# Dragino-MS14-S-Relay-Board.net
KiCad netlist of a schematic drawn in EAGLE
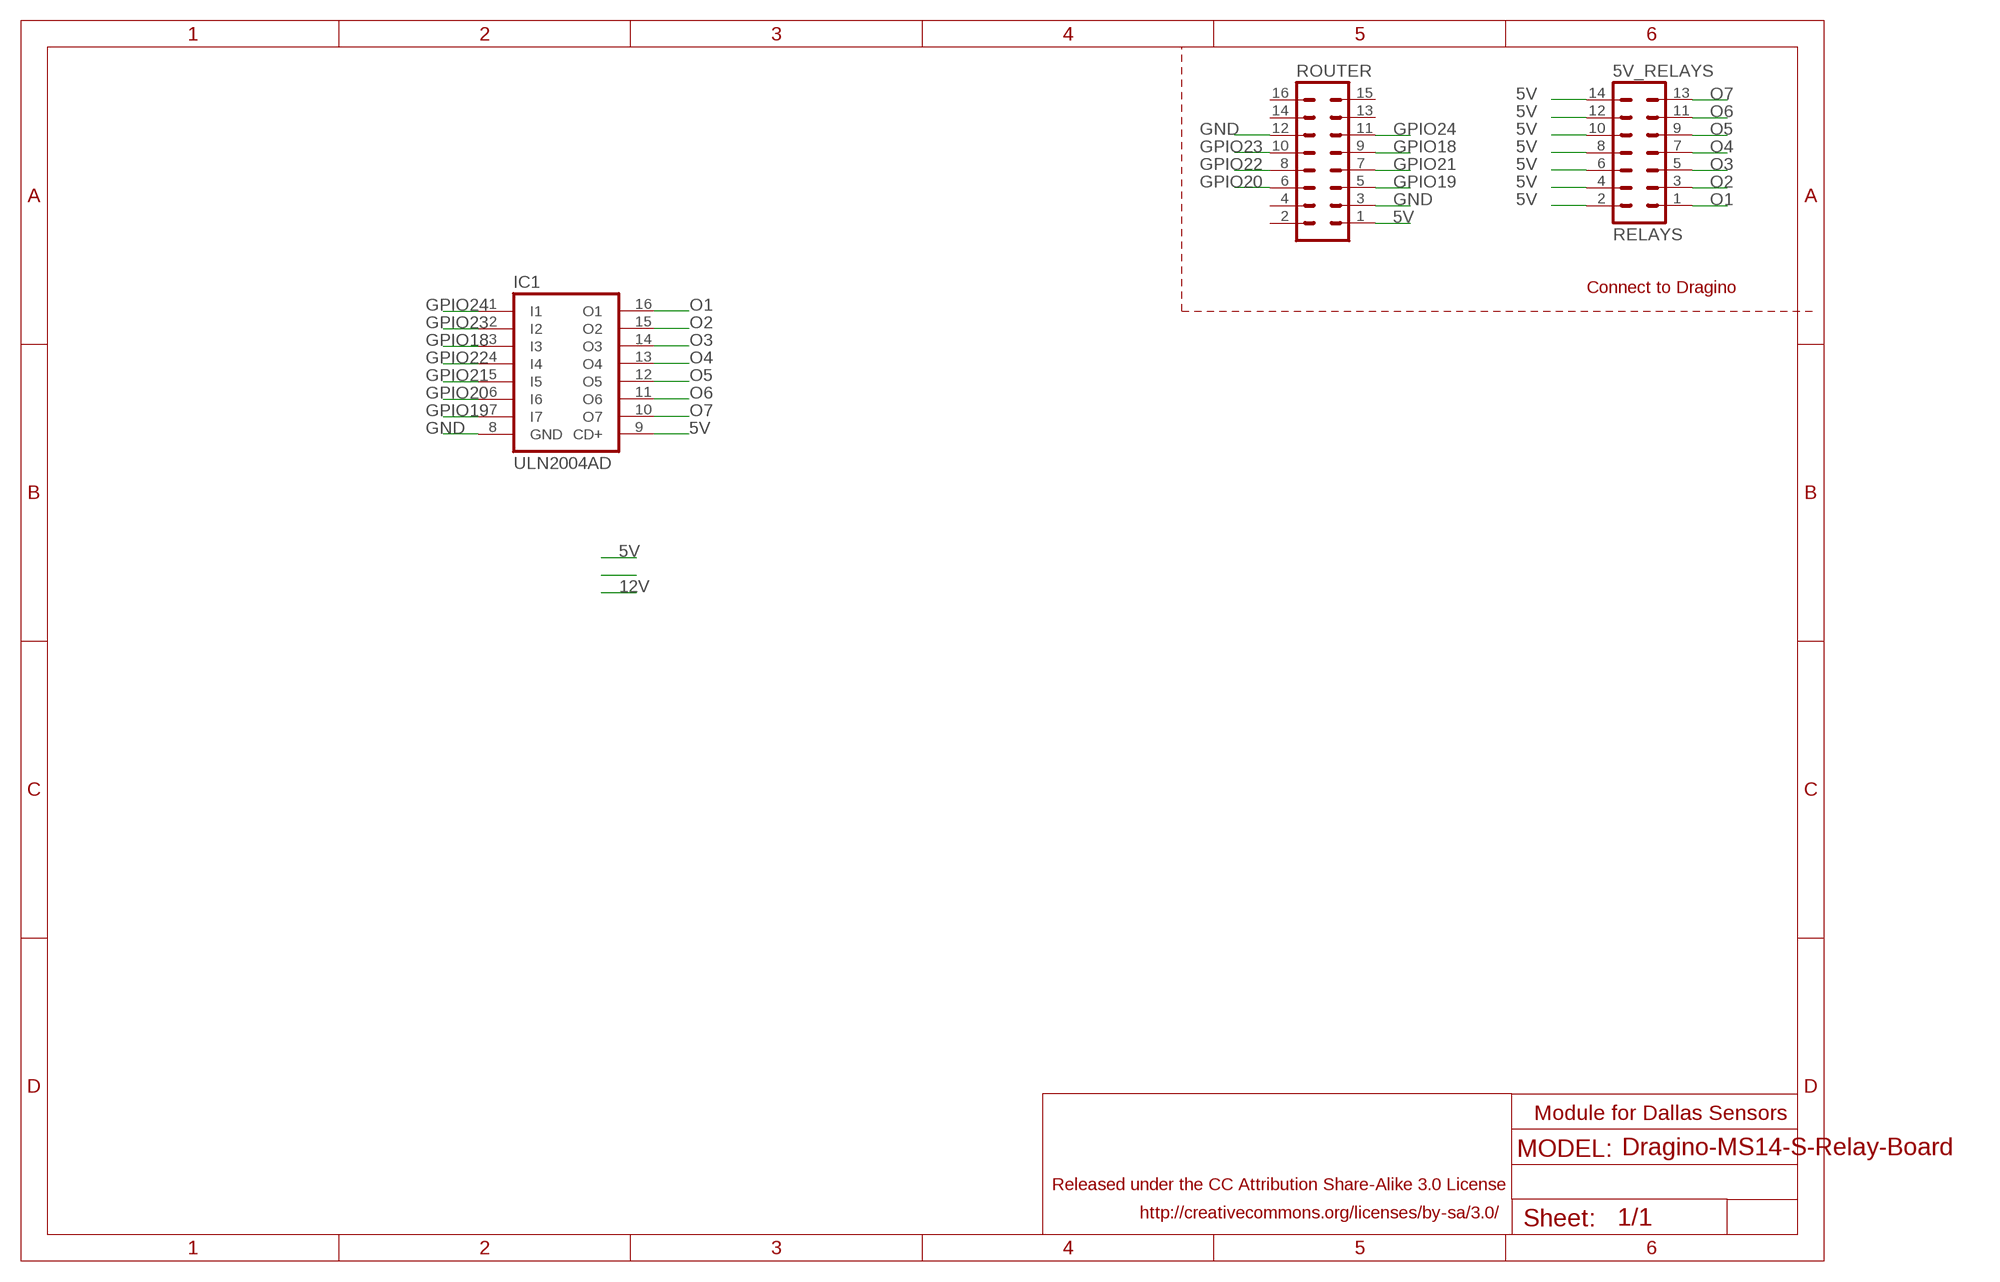
[diagram p0: schematic, sheet 1]

(export (version "E")
  (design (tool "Eeschema 10.0.6"))
  (components
    (comp (ref "5V_RELAYS")
      (value "RELAYS")
      (footprint "eagle-import:MA07-2")
      (libsource (lib "eagle-import") (part "MA07-2"))
    )
    (comp (ref "IC1")
      (value "ULN2004AD")
      (footprint "eagle-import:SO16")
      (libsource (lib "eagle-import") (part "ULN2004AD"))
    )
    (comp (ref "ROUTER")
      (value "MA08-2")
      (footprint "eagle-import:MA08-2")
      (libsource (lib "eagle-import") (part "MA08-2"))
    )
  )
  (nets
    (net (code "1") (name "/5V") (class "Default")
      (node (ref "5V_RELAYS") (pin "10") (pinfunction "10_10") (pintype "passive"))
      (node (ref "5V_RELAYS") (pin "12") (pinfunction "12_12") (pintype "passive"))
      (node (ref "5V_RELAYS") (pin "14") (pinfunction "14_14") (pintype "passive"))
      (node (ref "5V_RELAYS") (pin "2") (pinfunction "2_2") (pintype "passive"))
      (node (ref "5V_RELAYS") (pin "4") (pinfunction "4_4") (pintype "passive"))
      (node (ref "5V_RELAYS") (pin "6") (pinfunction "6_6") (pintype "passive"))
      (node (ref "5V_RELAYS") (pin "8") (pinfunction "8_8") (pintype "passive"))
      (node (ref "IC1") (pin "9") (pinfunction "CD+_9") (pintype "passive"))
      (node (ref "ROUTER") (pin "1") (pinfunction "1_1") (pintype "passive"))
    )
    (net (code "3") (name "/GND") (class "Default")
      (node (ref "IC1") (pin "8") (pinfunction "GND_8") (pintype "power_in"))
      (node (ref "ROUTER") (pin "12") (pinfunction "12_12") (pintype "passive"))
      (node (ref "ROUTER") (pin "3") (pinfunction "3_3") (pintype "passive"))
    )
    (net (code "4") (name "/GPIO18") (class "Default")
      (node (ref "IC1") (pin "3") (pinfunction "I3_3") (pintype "input"))
      (node (ref "ROUTER") (pin "9") (pinfunction "9_9") (pintype "passive"))
    )
    (net (code "5") (name "/GPIO19") (class "Default")
      (node (ref "IC1") (pin "7") (pinfunction "I7_7") (pintype "input"))
      (node (ref "ROUTER") (pin "5") (pinfunction "5_5") (pintype "passive"))
    )
    (net (code "6") (name "/GPIO20") (class "Default")
      (node (ref "IC1") (pin "6") (pinfunction "I6_6") (pintype "input"))
      (node (ref "ROUTER") (pin "6") (pinfunction "6_6") (pintype "passive"))
    )
    (net (code "7") (name "/GPIO21") (class "Default")
      (node (ref "IC1") (pin "5") (pinfunction "I5_5") (pintype "input"))
      (node (ref "ROUTER") (pin "7") (pinfunction "7_7") (pintype "passive"))
    )
    (net (code "8") (name "/GPIO22") (class "Default")
      (node (ref "IC1") (pin "4") (pinfunction "I4_4") (pintype "input"))
      (node (ref "ROUTER") (pin "8") (pinfunction "8_8") (pintype "passive"))
    )
    (net (code "9") (name "/GPIO23") (class "Default")
      (node (ref "IC1") (pin "2") (pinfunction "I2_2") (pintype "input"))
      (node (ref "ROUTER") (pin "10") (pinfunction "10_10") (pintype "passive"))
    )
    (net (code "10") (name "/GPIO24") (class "Default")
      (node (ref "IC1") (pin "1") (pinfunction "I1_1") (pintype "input"))
      (node (ref "ROUTER") (pin "11") (pinfunction "11_11") (pintype "passive"))
    )
    (net (code "11") (name "/O1") (class "Default")
      (node (ref "5V_RELAYS") (pin "1") (pinfunction "1_1") (pintype "passive"))
      (node (ref "IC1") (pin "16") (pinfunction "O1_16") (pintype "open_collector"))
    )
    (net (code "12") (name "/O2") (class "Default")
      (node (ref "5V_RELAYS") (pin "3") (pinfunction "3_3") (pintype "passive"))
      (node (ref "IC1") (pin "15") (pinfunction "O2_15") (pintype "open_collector"))
    )
    (net (code "13") (name "/O3") (class "Default")
      (node (ref "5V_RELAYS") (pin "5") (pinfunction "5_5") (pintype "passive"))
      (node (ref "IC1") (pin "14") (pinfunction "O3_14") (pintype "open_collector"))
    )
    (net (code "14") (name "/O4") (class "Default")
      (node (ref "5V_RELAYS") (pin "7") (pinfunction "7_7") (pintype "passive"))
      (node (ref "IC1") (pin "13") (pinfunction "O4_13") (pintype "open_collector"))
    )
    (net (code "15") (name "/O5") (class "Default")
      (node (ref "5V_RELAYS") (pin "9") (pinfunction "9_9") (pintype "passive"))
      (node (ref "IC1") (pin "12") (pinfunction "O5_12") (pintype "open_collector"))
    )
    (net (code "16") (name "/O6") (class "Default")
      (node (ref "5V_RELAYS") (pin "11") (pinfunction "11_11") (pintype "passive"))
      (node (ref "IC1") (pin "11") (pinfunction "O6_11") (pintype "open_collector"))
    )
    (net (code "17") (name "/O7") (class "Default")
      (node (ref "5V_RELAYS") (pin "13") (pinfunction "13_13") (pintype "passive"))
      (node (ref "IC1") (pin "10") (pinfunction "O7_10") (pintype "open_collector"))
    )
    (net (code "18") (name "unconnected-(ROUTER-Pad2)") (class "Default")
      (node (ref "ROUTER") (pin "2") (pinfunction "2_2") (pintype "passive"))
    )
    (net (code "19") (name "unconnected-(ROUTER-Pad4)") (class "Default")
      (node (ref "ROUTER") (pin "4") (pinfunction "4_4") (pintype "passive"))
    )
    (net (code "20") (name "unconnected-(ROUTER-Pad13)") (class "Default")
      (node (ref "ROUTER") (pin "13") (pinfunction "13_13") (pintype "passive"))
    )
    (net (code "21") (name "unconnected-(ROUTER-Pad14)") (class "Default")
      (node (ref "ROUTER") (pin "14") (pinfunction "14_14") (pintype "passive"))
    )
    (net (code "22") (name "unconnected-(ROUTER-Pad15)") (class "Default")
      (node (ref "ROUTER") (pin "15") (pinfunction "15_15") (pintype "passive"))
    )
    (net (code "23") (name "unconnected-(ROUTER-Pad16)") (class "Default")
      (node (ref "ROUTER") (pin "16") (pinfunction "16_16") (pintype "passive"))
    )
  )
)
